# Data.net
KiCad netlist of a schematic drawn in Altium Designer
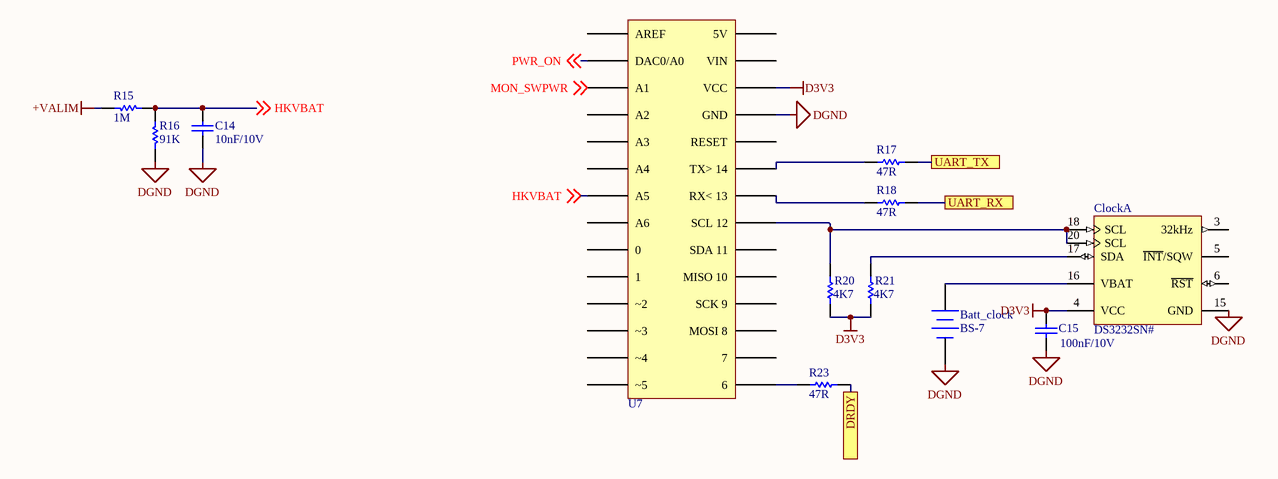
[diagram p0: Data.SchDoc]

(export (version "E")
  (design (tool "Eeschema 10.0.6"))
  (components
    (comp (ref "Batt_clock")
      (value "BS-7")
      (footprint "BS-7-ND")
      (description "BS-7 CR2032 battery holder")
      (fields (field (name "PUBLISHER") "Altium Limited"))
      (libsource (lib "Components") (part "BS-7"))
    )
    (comp (ref "C14")
      (value "10nF/10V")
      (footprint "0603")
      (description "Ceramic Chip Capacitor - Standard")
      (fields (field (name "Comment") "C0603") (field (name "PUBLISHER") "Altium Limited"))
      (libsource (lib "KEMET Chip Capacitor") (part "C0603"))
    )
    (comp (ref "C15")
      (value "100nF/10V")
      (footprint "0805")
      (description "Ceramic Chip Capacitor - Standard")
      (fields (field (name "Comment") "C0805") (field (name "PUBLISHER") "Altium Limited"))
      (libsource (lib "KEMET Chip Capacitor") (part "C0805"))
    )
    (comp (ref "Clock")
      (value "DS3232SN#")
      (footprint "W20#H2_N")
      (libsource (lib "Altium Content Vault") (part "MAX-RTC-20-DS3232S-W20#H2"))
    )
    (comp (ref "R15")
      (value "1M")
      (footprint "0603")
      (description "Resistor")
      (fields (field (name "Comment") "Res CMS") (field (name "PUBLISHER") "Altium Limited"))
      (libsource (lib "Components") (part "Res CMS"))
    )
    (comp (ref "R16")
      (value "91K")
      (footprint "0603")
      (description "Resistor")
      (fields (field (name "Comment") "Res CMS") (field (name "PUBLISHER") "Altium Limited"))
      (libsource (lib "Components") (part "Res CMS"))
    )
    (comp (ref "R17")
      (value "47R")
      (footprint "0603")
      (description "Resistor")
      (fields (field (name "Comment") "Res CMS") (field (name "PUBLISHER") "Altium Limited"))
      (libsource (lib "Components") (part "Res CMS"))
    )
    (comp (ref "R18")
      (value "47R")
      (footprint "0603")
      (description "Resistor")
      (fields (field (name "Comment") "Res CMS") (field (name "PUBLISHER") "Altium Limited"))
      (libsource (lib "Components") (part "Res CMS"))
    )
    (comp (ref "R20")
      (value "4K7")
      (footprint "0603")
      (description "Resistor")
      (fields (field (name "Comment") "Res CMS") (field (name "PUBLISHER") "Altium Limited"))
      (libsource (lib "Components") (part "Res CMS"))
    )
    (comp (ref "R21")
      (value "4K7")
      (footprint "0603")
      (description "Resistor")
      (fields (field (name "Comment") "Res CMS") (field (name "PUBLISHER") "Altium Limited"))
      (libsource (lib "Components") (part "Res CMS"))
    )
    (comp (ref "R23")
      (value "47R")
      (footprint "0603")
      (description "Resistor")
      (fields (field (name "Comment") "Res CMS") (field (name "PUBLISHER") "Altium Limited"))
      (libsource (lib "Components") (part "Res CMS"))
    )
    (comp (ref "U7")
      (value "Arduino MKRZero")
      (footprint "Arduino MKRZero")
      (libsource (lib "Components") (part "Arduino MKRZero"))
    )
  )
  (nets
    (net (code "1") (name "+VALIM") (class "Default")
      (node (ref "R15") (pin "2") (pinfunction "2_2") (pintype "passive"))
    )
    (net (code "2") (name "/DRDY") (class "Default")
      (node (ref "R23") (pin "1") (pinfunction "1_1") (pintype "passive"))
    )
    (net (code "3") (name "/UART_RX") (class "Default")
      (node (ref "R18") (pin "1") (pinfunction "1_1") (pintype "passive"))
    )
    (net (code "4") (name "/UART_TX") (class "Default")
      (node (ref "R17") (pin "1") (pinfunction "1_1") (pintype "passive"))
    )
    (net (code "5") (name "D3V3") (class "Default")
      (node (ref "C15") (pin "1") (pinfunction "1_1") (pintype "passive"))
      (node (ref "Clock") (pin "4") (pinfunction "VCC_4") (pintype "power_in"))
      (node (ref "R20") (pin "1") (pinfunction "1_1") (pintype "passive"))
      (node (ref "R21") (pin "1") (pinfunction "1_1") (pintype "passive"))
      (node (ref "U7") (pin "26") (pinfunction "VCC_26") (pintype "passive"))
    )
    (net (code "6") (name "DGND") (class "Default")
      (node (ref "Batt_clock") (pin "2") (pinfunction "-_2") (pintype "passive"))
      (node (ref "C14") (pin "1") (pinfunction "1_1") (pintype "passive"))
      (node (ref "C15") (pin "2") (pinfunction "2_2") (pintype "passive"))
      (node (ref "Clock") (pin "15") (pinfunction "GND_15") (pintype "power_in"))
      (node (ref "R16") (pin "2") (pinfunction "2_2") (pintype "passive"))
      (node (ref "U7") (pin "25") (pinfunction "GND_25") (pintype "passive"))
    )
    (net (code "7") (name "HKVBAT") (class "Default")
      (node (ref "C14") (pin "2") (pinfunction "2_2") (pintype "passive"))
      (node (ref "R15") (pin "1") (pinfunction "1_1") (pintype "passive"))
      (node (ref "R16") (pin "1") (pinfunction "1_1") (pintype "passive"))
      (node (ref "U7") (pin "7") (pinfunction "A5_7") (pintype "passive"))
    )
    (net (code "8") (name "MON_SWPWR") (class "Default")
      (node (ref "U7") (pin "3") (pinfunction "A1_3") (pintype "passive"))
    )
    (net (code "9") (name "Net-(Batt_clock-+)") (class "Default")
      (node (ref "Batt_clock") (pin "1") (pinfunction "+_1") (pintype "passive"))
      (node (ref "Clock") (pin "16") (pinfunction "VBAT_16") (pintype "power_in"))
    )
    (net (code "10") (name "Net-(ClockA-SDA)") (class "Default")
      (node (ref "Clock") (pin "17") (pinfunction "SDA_17") (pintype "bidirectional"))
      (node (ref "R21") (pin "2") (pinfunction "2_2") (pintype "passive"))
    )
    (net (code "11") (name "Net-(U7-6)") (class "Default")
      (node (ref "R23") (pin "2") (pinfunction "2_2") (pintype "passive"))
      (node (ref "U7") (pin "15") (pinfunction "6_15") (pintype "passive"))
    )
    (net (code "12") (name "Net-(U7-RX<_13)") (class "Default")
      (node (ref "R18") (pin "2") (pinfunction "2_2") (pintype "passive"))
      (node (ref "U7") (pin "22") (pinfunction "RX<_13_22") (pintype "passive"))
    )
    (net (code "13") (name "Net-(U7-SCL_12)") (class "Default")
      (node (ref "Clock") (pin "18") (pinfunction "SCL_18") (pintype "input"))
      (node (ref "Clock") (pin "20") (pinfunction "SCL_20") (pintype "input"))
      (node (ref "R20") (pin "2") (pinfunction "2_2") (pintype "passive"))
      (node (ref "U7") (pin "21") (pinfunction "SCL_12_21") (pintype "passive"))
    )
    (net (code "14") (name "Net-(U7-TX>_14)") (class "Default")
      (node (ref "R17") (pin "2") (pinfunction "2_2") (pintype "passive"))
      (node (ref "U7") (pin "23") (pinfunction "TX>_14_23") (pintype "passive"))
    )
    (net (code "15") (name "PWR_ON") (class "Default")
      (node (ref "U7") (pin "2") (pinfunction "DAC0/A0_2") (pintype "passive"))
    )
    (net (code "16") (name "unconnected-(ClockA-32kHz-Pad3)") (class "Default")
      (node (ref "Clock") (pin "3") (pinfunction "32kHz_3") (pintype "output"))
    )
    (net (code "17") (name "unconnected-(ClockA-~{INT}{slash}SQW-Pad5)") (class "Default")
      (node (ref "Clock") (pin "5") (pinfunction "~{INT}/SQW_5") (pintype "open_collector"))
    )
    (net (code "18") (name "unconnected-(ClockA-~{RST}-Pad6)") (class "Default")
      (node (ref "Clock") (pin "6") (pinfunction "~{RST}_6") (pintype "bidirectional"))
    )
    (net (code "19") (name "unconnected-(U7-0-Pad9)") (class "Default")
      (node (ref "U7") (pin "9") (pinfunction "0_9") (pintype "passive"))
    )
    (net (code "20") (name "unconnected-(U7-1-Pad10)") (class "Default")
      (node (ref "U7") (pin "10") (pinfunction "1_10") (pintype "passive"))
    )
    (net (code "21") (name "unconnected-(U7-5V-Pad28)") (class "Default")
      (node (ref "U7") (pin "28") (pinfunction "5V_28") (pintype "passive"))
    )
    (net (code "22") (name "unconnected-(U7-7-Pad16)") (class "Default")
      (node (ref "U7") (pin "16") (pinfunction "7_16") (pintype "passive"))
    )
    (net (code "23") (name "unconnected-(U7-A2-Pad4)") (class "Default")
      (node (ref "U7") (pin "4") (pinfunction "A2_4") (pintype "passive"))
    )
    (net (code "24") (name "unconnected-(U7-A3-Pad5)") (class "Default")
      (node (ref "U7") (pin "5") (pinfunction "A3_5") (pintype "passive"))
    )
    (net (code "25") (name "unconnected-(U7-A4-Pad6)") (class "Default")
      (node (ref "U7") (pin "6") (pinfunction "A4_6") (pintype "passive"))
    )
    (net (code "26") (name "unconnected-(U7-A6-Pad8)") (class "Default")
      (node (ref "U7") (pin "8") (pinfunction "A6_8") (pintype "passive"))
    )
    (net (code "27") (name "unconnected-(U7-AREF-Pad1)") (class "Default")
      (node (ref "U7") (pin "1") (pinfunction "AREF_1") (pintype "passive"))
    )
    (net (code "28") (name "unconnected-(U7-MISO_10-Pad19)") (class "Default")
      (node (ref "U7") (pin "19") (pinfunction "MISO_10_19") (pintype "passive"))
    )
    (net (code "29") (name "unconnected-(U7-MOSI_8-Pad17)") (class "Default")
      (node (ref "U7") (pin "17") (pinfunction "MOSI_8_17") (pintype "passive"))
    )
    (net (code "30") (name "unconnected-(U7-RESET-Pad24)") (class "Default")
      (node (ref "U7") (pin "24") (pinfunction "RESET_24") (pintype "passive"))
    )
    (net (code "31") (name "unconnected-(U7-SCK_9-Pad18)") (class "Default")
      (node (ref "U7") (pin "18") (pinfunction "SCK_9_18") (pintype "passive"))
    )
    (net (code "32") (name "unconnected-(U7-SDA_11-Pad20)") (class "Default")
      (node (ref "U7") (pin "20") (pinfunction "SDA_11_20") (pintype "passive"))
    )
    (net (code "33") (name "unconnected-(U7-VIN-Pad27)") (class "Default")
      (node (ref "U7") (pin "27") (pinfunction "VIN_27") (pintype "passive"))
    )
    (net (code "34") (name "unconnected-(U7-~2-Pad11)") (class "Default")
      (node (ref "U7") (pin "11") (pinfunction "~2_11") (pintype "passive"))
    )
    (net (code "35") (name "unconnected-(U7-~3-Pad12)") (class "Default")
      (node (ref "U7") (pin "12") (pinfunction "~3_12") (pintype "passive"))
    )
    (net (code "36") (name "unconnected-(U7-~4-Pad13)") (class "Default")
      (node (ref "U7") (pin "13") (pinfunction "~4_13") (pintype "passive"))
    )
    (net (code "37") (name "unconnected-(U7-~5-Pad14)") (class "Default")
      (node (ref "U7") (pin "14") (pinfunction "~5_14") (pintype "passive"))
    )
  )
)
